# ESP_SCH.net
KiCad netlist of a schematic drawn in EAGLE
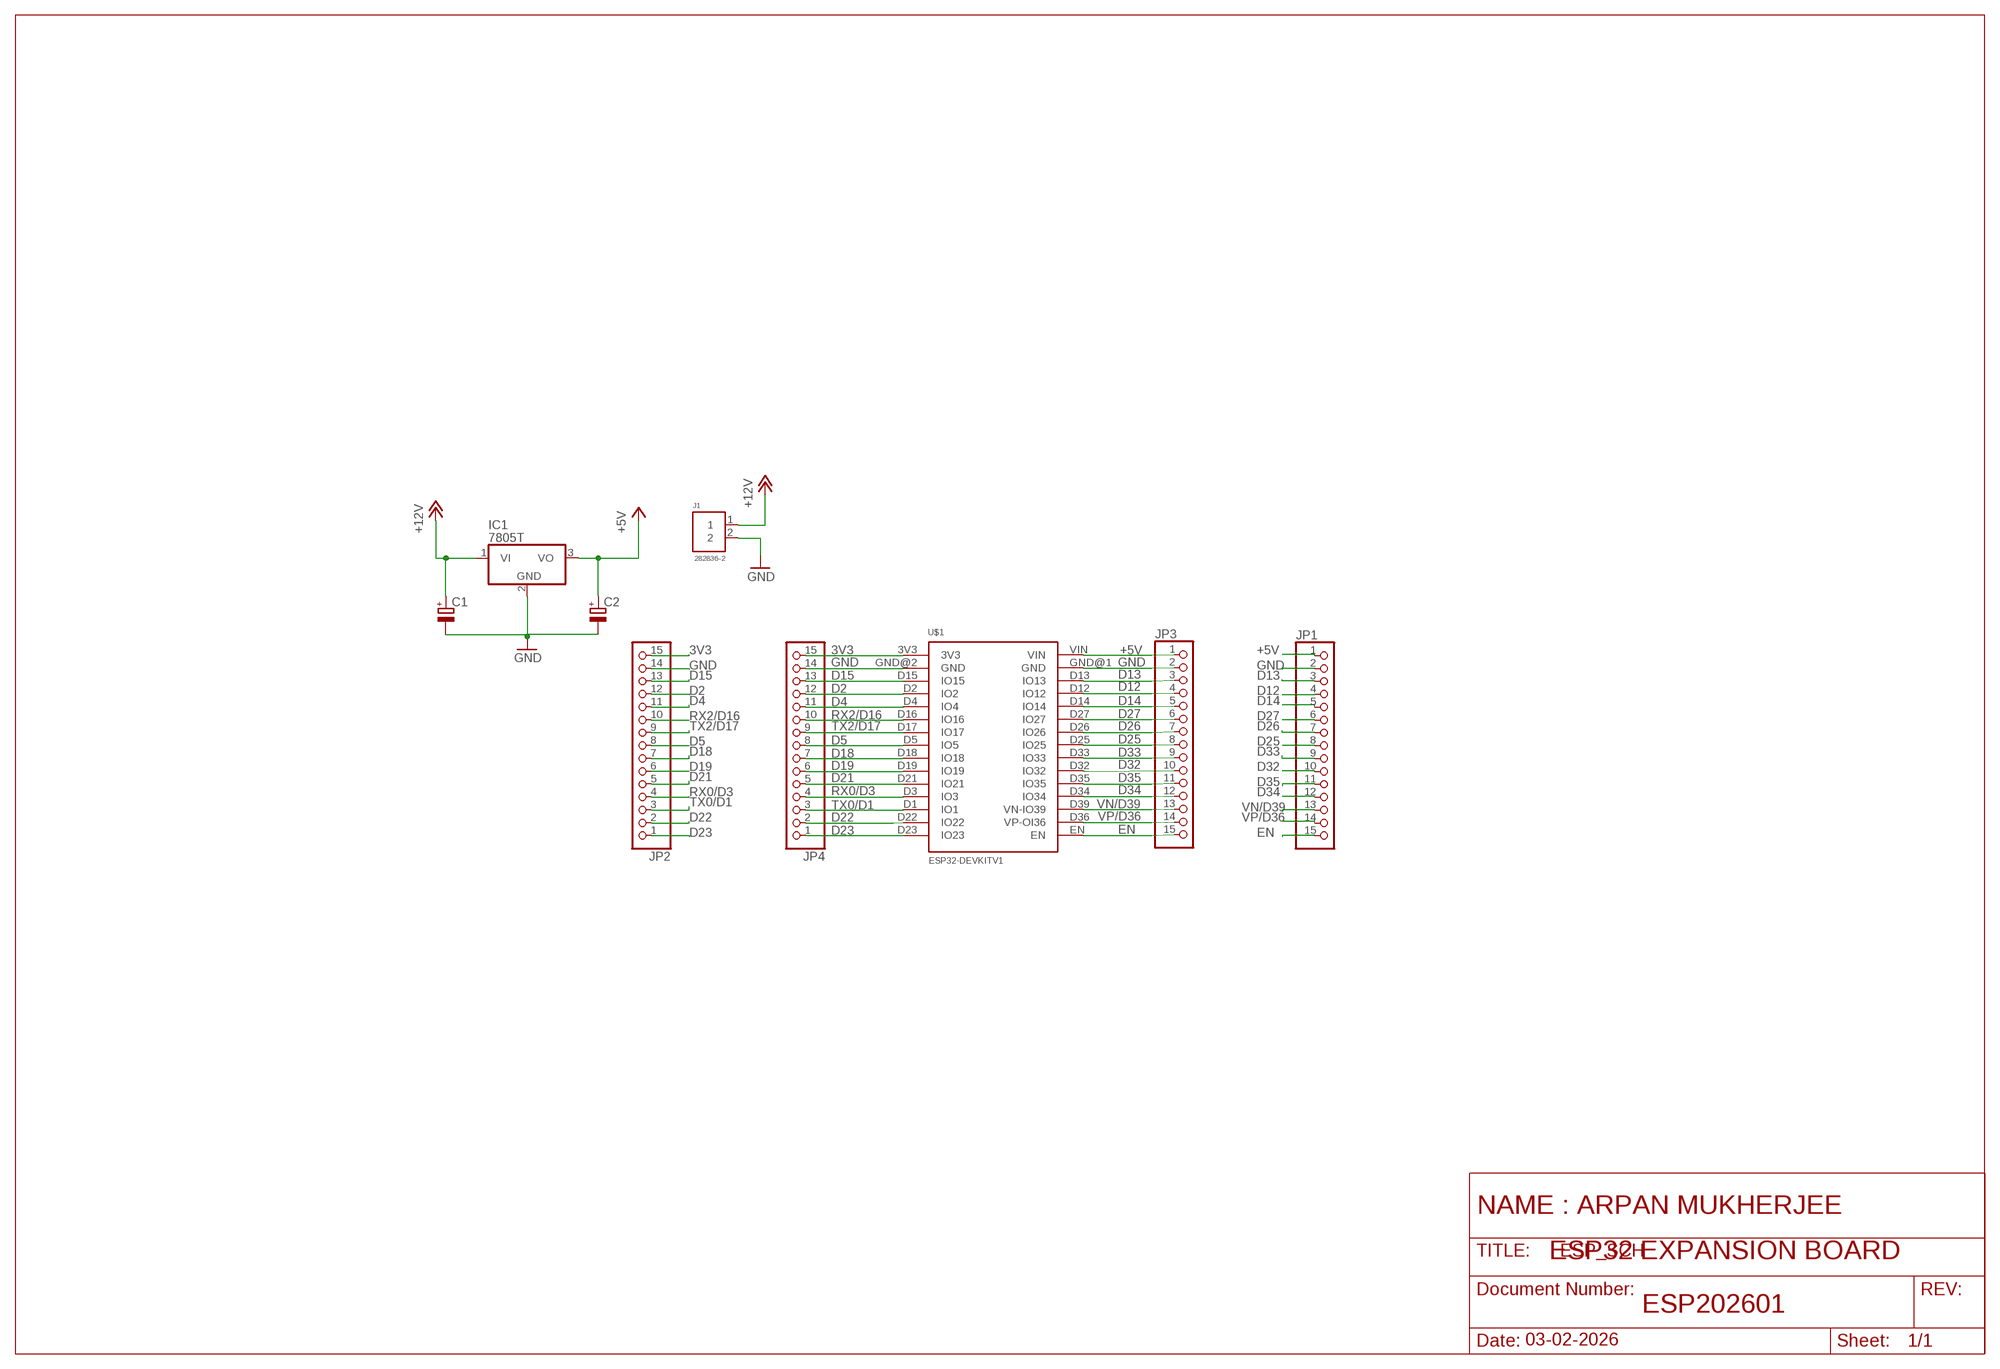
[diagram p0: schematic, sheet 1]

(export (version "E")
  (design (tool "Eeschema 10.0.6"))
  (components
    (comp (ref "C1")
      (value "CPOL-EUE2.5-5")
      (footprint "eagle-import:E2,5-5")
      (libsource (lib "eagle-import") (part "CPOL-EUE2.5-5"))
    )
    (comp (ref "C2")
      (value "CPOL-EUE2.5-5")
      (footprint "eagle-import:E2,5-5")
      (libsource (lib "eagle-import") (part "CPOL-EUE2.5-5"))
    )
    (comp (ref "IC1")
      (value "7805T")
      (footprint "eagle-import:TO220H")
      (libsource (lib "eagle-import") (part "78T05"))
    )
    (comp (ref "J1")
      (value "282836-2")
      (footprint "eagle-import:CONN_282836-2")
      (fields (field (name "MF") "TE Connectivity"))
      (libsource (lib "eagle-import") (part "282836-2"))
    )
    (comp (ref "JP1")
      (value "PINHD-1X15")
      (footprint "eagle-import:1X15")
      (libsource (lib "eagle-import") (part "PINHD-1X15"))
    )
    (comp (ref "JP2")
      (value "PINHD-1X15")
      (footprint "eagle-import:1X15")
      (libsource (lib "eagle-import") (part "PINHD-1X15"))
    )
    (comp (ref "JP3")
      (value "PINHD-1X15")
      (footprint "eagle-import:1X15")
      (libsource (lib "eagle-import") (part "PINHD-1X15"))
    )
    (comp (ref "JP4")
      (value "PINHD-1X15")
      (footprint "eagle-import:1X15")
      (libsource (lib "eagle-import") (part "PINHD-1X15"))
    )
    (comp (ref "U$1")
      (value "ESP32DEVKITV1")
      (footprint "eagle-import:ESP32-DEVKITV1")
      (libsource (lib "eagle-import") (part "ESP32DEVKITV1"))
    )
  )
  (nets
    (net (code "1") (name "+5V") (class "Default")
      (node (ref "C2") (pin "+") (pinfunction "+_+") (pintype "passive"))
      (node (ref "IC1") (pin "3") (pinfunction "VO_3") (pintype "passive"))
      (node (ref "JP1") (pin "1") (pinfunction "1_1") (pintype "passive"))
      (node (ref "JP3") (pin "1") (pinfunction "1_1") (pintype "passive"))
      (node (ref "U$1") (pin "VIN") (pinfunction "VIN_VIN") (pintype "bidirectional"))
    )
    (net (code "2") (name "+12V") (class "Default")
      (node (ref "C1") (pin "+") (pinfunction "+_+") (pintype "passive"))
      (node (ref "IC1") (pin "1") (pinfunction "VI_1") (pintype "input"))
      (node (ref "J1") (pin "1") (pinfunction "1_1") (pintype "passive"))
    )
    (net (code "3") (name "/3V3") (class "Default")
      (node (ref "JP2") (pin "15") (pinfunction "15_15") (pintype "passive"))
      (node (ref "JP4") (pin "15") (pinfunction "15_15") (pintype "passive"))
      (node (ref "U$1") (pin "3V3") (pinfunction "3V3_3V3") (pintype "bidirectional"))
    )
    (net (code "4") (name "/D2") (class "Default")
      (node (ref "JP2") (pin "12") (pinfunction "12_12") (pintype "passive"))
      (node (ref "JP4") (pin "12") (pinfunction "12_12") (pintype "passive"))
      (node (ref "U$1") (pin "D2") (pinfunction "IO2_D2") (pintype "bidirectional"))
    )
    (net (code "5") (name "/D4") (class "Default")
      (node (ref "JP2") (pin "11") (pinfunction "11_11") (pintype "passive"))
      (node (ref "JP4") (pin "11") (pinfunction "11_11") (pintype "passive"))
      (node (ref "U$1") (pin "D4") (pinfunction "IO4_D4") (pintype "bidirectional"))
    )
    (net (code "6") (name "/D5") (class "Default")
      (node (ref "JP2") (pin "8") (pinfunction "8_8") (pintype "passive"))
      (node (ref "JP4") (pin "8") (pinfunction "8_8") (pintype "passive"))
      (node (ref "U$1") (pin "D5") (pinfunction "IO5_D5") (pintype "bidirectional"))
    )
    (net (code "7") (name "/D12") (class "Default")
      (node (ref "JP1") (pin "4") (pinfunction "4_4") (pintype "passive"))
      (node (ref "JP3") (pin "4") (pinfunction "4_4") (pintype "passive"))
      (node (ref "U$1") (pin "D12") (pinfunction "IO12_D12") (pintype "bidirectional"))
    )
    (net (code "8") (name "/D13") (class "Default")
      (node (ref "JP1") (pin "3") (pinfunction "3_3") (pintype "passive"))
      (node (ref "JP3") (pin "3") (pinfunction "3_3") (pintype "passive"))
      (node (ref "U$1") (pin "D13") (pinfunction "IO13_D13") (pintype "bidirectional"))
    )
    (net (code "9") (name "/D14") (class "Default")
      (node (ref "JP1") (pin "5") (pinfunction "5_5") (pintype "passive"))
      (node (ref "JP3") (pin "5") (pinfunction "5_5") (pintype "passive"))
      (node (ref "U$1") (pin "D14") (pinfunction "IO14_D14") (pintype "bidirectional"))
    )
    (net (code "10") (name "/D15") (class "Default")
      (node (ref "JP2") (pin "13") (pinfunction "13_13") (pintype "passive"))
      (node (ref "JP4") (pin "13") (pinfunction "13_13") (pintype "passive"))
      (node (ref "U$1") (pin "D15") (pinfunction "IO15_D15") (pintype "bidirectional"))
    )
    (net (code "11") (name "/D18") (class "Default")
      (node (ref "JP2") (pin "7") (pinfunction "7_7") (pintype "passive"))
      (node (ref "JP4") (pin "7") (pinfunction "7_7") (pintype "passive"))
      (node (ref "U$1") (pin "D18") (pinfunction "IO18_D18") (pintype "bidirectional"))
    )
    (net (code "12") (name "/D19") (class "Default")
      (node (ref "JP2") (pin "6") (pinfunction "6_6") (pintype "passive"))
      (node (ref "JP4") (pin "6") (pinfunction "6_6") (pintype "passive"))
      (node (ref "U$1") (pin "D19") (pinfunction "IO19_D19") (pintype "bidirectional"))
    )
    (net (code "13") (name "/D21") (class "Default")
      (node (ref "JP2") (pin "5") (pinfunction "5_5") (pintype "passive"))
      (node (ref "JP4") (pin "5") (pinfunction "5_5") (pintype "passive"))
      (node (ref "U$1") (pin "D21") (pinfunction "IO21_D21") (pintype "bidirectional"))
    )
    (net (code "14") (name "/D22") (class "Default")
      (node (ref "JP2") (pin "2") (pinfunction "2_2") (pintype "passive"))
      (node (ref "JP4") (pin "2") (pinfunction "2_2") (pintype "passive"))
      (node (ref "U$1") (pin "D22") (pinfunction "IO22_D22") (pintype "bidirectional"))
    )
    (net (code "15") (name "/D23") (class "Default")
      (node (ref "JP2") (pin "1") (pinfunction "1_1") (pintype "passive"))
      (node (ref "JP4") (pin "1") (pinfunction "1_1") (pintype "passive"))
      (node (ref "U$1") (pin "D23") (pinfunction "IO23_D23") (pintype "bidirectional"))
    )
    (net (code "16") (name "/D25") (class "Default")
      (node (ref "JP1") (pin "8") (pinfunction "8_8") (pintype "passive"))
      (node (ref "JP3") (pin "8") (pinfunction "8_8") (pintype "passive"))
      (node (ref "U$1") (pin "D25") (pinfunction "IO25_D25") (pintype "bidirectional"))
    )
    (net (code "17") (name "/D26") (class "Default")
      (node (ref "JP1") (pin "7") (pinfunction "7_7") (pintype "passive"))
      (node (ref "JP3") (pin "7") (pinfunction "7_7") (pintype "passive"))
      (node (ref "U$1") (pin "D26") (pinfunction "IO26_D26") (pintype "bidirectional"))
    )
    (net (code "18") (name "/D27") (class "Default")
      (node (ref "JP1") (pin "6") (pinfunction "6_6") (pintype "passive"))
      (node (ref "JP3") (pin "6") (pinfunction "6_6") (pintype "passive"))
      (node (ref "U$1") (pin "D27") (pinfunction "IO27_D27") (pintype "bidirectional"))
    )
    (net (code "19") (name "/D32") (class "Default")
      (node (ref "JP1") (pin "10") (pinfunction "10_10") (pintype "passive"))
      (node (ref "JP3") (pin "10") (pinfunction "10_10") (pintype "passive"))
      (node (ref "U$1") (pin "D32") (pinfunction "IO32_D32") (pintype "bidirectional"))
    )
    (net (code "20") (name "/D33") (class "Default")
      (node (ref "JP1") (pin "9") (pinfunction "9_9") (pintype "passive"))
      (node (ref "JP3") (pin "9") (pinfunction "9_9") (pintype "passive"))
      (node (ref "U$1") (pin "D33") (pinfunction "IO33_D33") (pintype "bidirectional"))
    )
    (net (code "21") (name "/D34") (class "Default")
      (node (ref "JP1") (pin "12") (pinfunction "12_12") (pintype "passive"))
      (node (ref "JP3") (pin "12") (pinfunction "12_12") (pintype "passive"))
      (node (ref "U$1") (pin "D34") (pinfunction "IO34_D34") (pintype "bidirectional"))
    )
    (net (code "22") (name "/D35") (class "Default")
      (node (ref "JP1") (pin "11") (pinfunction "11_11") (pintype "passive"))
      (node (ref "JP3") (pin "11") (pinfunction "11_11") (pintype "passive"))
      (node (ref "U$1") (pin "D35") (pinfunction "IO35_D35") (pintype "bidirectional"))
    )
    (net (code "23") (name "/EN") (class "Default")
      (node (ref "JP1") (pin "15") (pinfunction "15_15") (pintype "passive"))
      (node (ref "JP3") (pin "15") (pinfunction "15_15") (pintype "passive"))
      (node (ref "U$1") (pin "EN") (pinfunction "EN_EN") (pintype "bidirectional"))
    )
    (net (code "24") (name "/RX0{slash}D3") (class "Default")
      (node (ref "JP2") (pin "4") (pinfunction "4_4") (pintype "passive"))
      (node (ref "JP4") (pin "4") (pinfunction "4_4") (pintype "passive"))
      (node (ref "U$1") (pin "D3") (pinfunction "IO3_D3") (pintype "bidirectional"))
    )
    (net (code "25") (name "/RX2{slash}D16") (class "Default")
      (node (ref "JP2") (pin "10") (pinfunction "10_10") (pintype "passive"))
      (node (ref "JP4") (pin "10") (pinfunction "10_10") (pintype "passive"))
      (node (ref "U$1") (pin "D16") (pinfunction "IO16_D16") (pintype "bidirectional"))
    )
    (net (code "26") (name "/TX0{slash}D1") (class "Default")
      (node (ref "JP2") (pin "3") (pinfunction "3_3") (pintype "passive"))
      (node (ref "JP4") (pin "3") (pinfunction "3_3") (pintype "passive"))
      (node (ref "U$1") (pin "D1") (pinfunction "IO1_D1") (pintype "bidirectional"))
    )
    (net (code "27") (name "/TX2{slash}D17") (class "Default")
      (node (ref "JP2") (pin "9") (pinfunction "9_9") (pintype "passive"))
      (node (ref "JP4") (pin "9") (pinfunction "9_9") (pintype "passive"))
      (node (ref "U$1") (pin "D17") (pinfunction "IO17_D17") (pintype "bidirectional"))
    )
    (net (code "28") (name "/VN{slash}D39") (class "Default")
      (node (ref "JP1") (pin "13") (pinfunction "13_13") (pintype "passive"))
      (node (ref "JP3") (pin "13") (pinfunction "13_13") (pintype "passive"))
      (node (ref "U$1") (pin "D39") (pinfunction "VN-IO39_D39") (pintype "bidirectional"))
    )
    (net (code "29") (name "/VP{slash}D36") (class "Default")
      (node (ref "JP1") (pin "14") (pinfunction "14_14") (pintype "passive"))
      (node (ref "JP3") (pin "14") (pinfunction "14_14") (pintype "passive"))
      (node (ref "U$1") (pin "D36") (pinfunction "VP-OI36_D36") (pintype "bidirectional"))
    )
    (net (code "30") (name "GND") (class "Default")
      (node (ref "C1") (pin "-") (pinfunction "-_-") (pintype "passive"))
      (node (ref "C2") (pin "-") (pinfunction "-_-") (pintype "passive"))
      (node (ref "IC1") (pin "2") (pinfunction "GND_2") (pintype "passive"))
      (node (ref "J1") (pin "2") (pinfunction "2_2") (pintype "passive"))
      (node (ref "JP1") (pin "2") (pinfunction "2_2") (pintype "passive"))
      (node (ref "JP2") (pin "14") (pinfunction "14_14") (pintype "passive"))
      (node (ref "JP3") (pin "2") (pinfunction "2_2") (pintype "passive"))
      (node (ref "JP4") (pin "14") (pinfunction "14_14") (pintype "passive"))
      (node (ref "U$1") (pin "GND@1") (pinfunction "GND_GND@1") (pintype "bidirectional"))
      (node (ref "U$1") (pin "GND@2") (pinfunction "GND_GND@2") (pintype "bidirectional"))
    )
  )
)
